# DIGITAL_OUTPUTS_BLOCK_B.net
KiCad netlist of a schematic drawn in Altium Designer
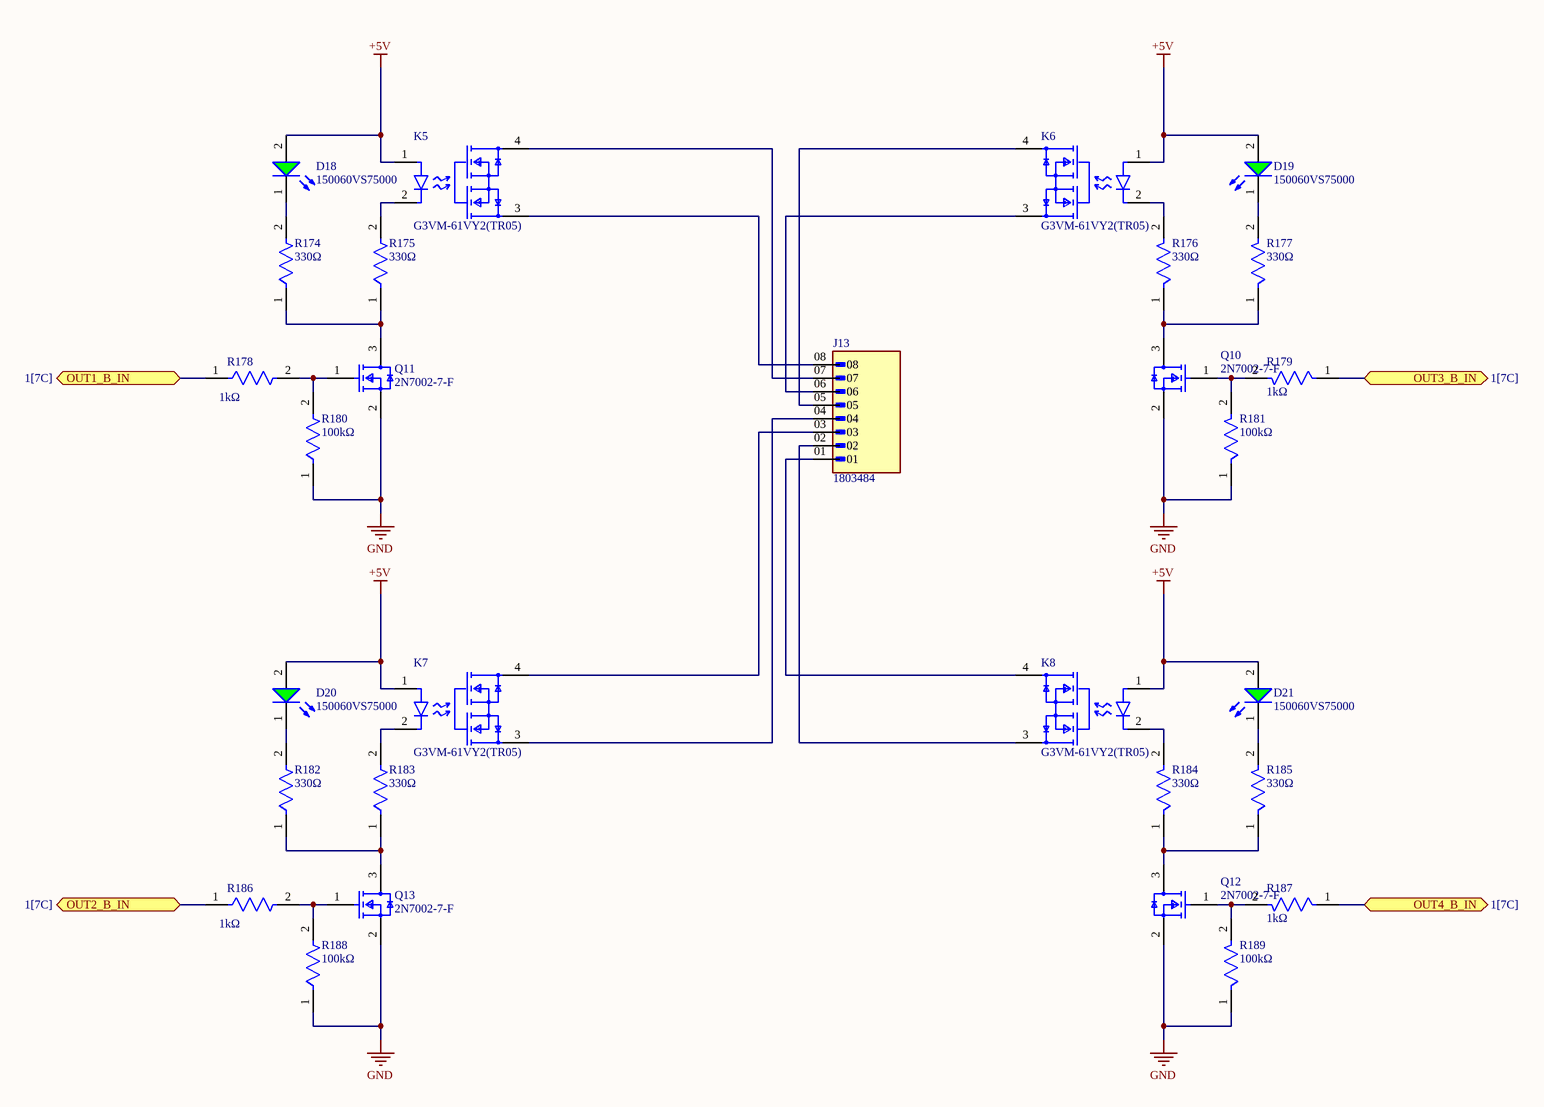
[diagram p0: DIGITAL_OUTPUTS_BLOCK_B.SchDoc]

(export (version "E")
  (design (tool "Eeschema 10.0.6"))
  (components
    (comp (ref "D18")
      (value "150060VS75000")
      (footprint "WL-SMCW_0603_150060xx75000")
      (libsource (lib "Altium Content Vault") (part "LED_Green_2A-1K"))
    )
    (comp (ref "D19")
      (value "150060VS75000")
      (footprint "WL-SMCW_0603_150060xx75000")
      (libsource (lib "Altium Content Vault") (part "LED_Green_2A-1K"))
    )
    (comp (ref "D20")
      (value "150060VS75000")
      (footprint "WL-SMCW_0603_150060xx75000")
      (libsource (lib "Altium Content Vault") (part "LED_Green_2A-1K"))
    )
    (comp (ref "D21")
      (value "150060VS75000")
      (footprint "WL-SMCW_0603_150060xx75000")
      (libsource (lib "Altium Content Vault") (part "LED_Green_2A-1K"))
    )
    (comp (ref "J13")
      (value "1803484")
      (footprint "1803484:PHOENIX_1803484")
      (fields (field (name "MF") "{'manufacturer': u'Phoenix Contact'}"))
      (libsource (lib "*") (part "1803484"))
    )
    (comp (ref "K5")
      (value "G3VM-61VY2(TR05)")
      (footprint "FP-G3VM-61VY2_TR05-MFG")
      (description "SSR RELAY SPST-NO 500MA 0-60V")
      (libsource (lib "Altium Content Vault") (part "39108d2c2fe9c6c4263f1aa8ae40286"))
    )
    (comp (ref "K6")
      (value "G3VM-61VY2(TR05)")
      (footprint "FP-G3VM-61VY2_TR05-MFG")
      (description "SSR RELAY SPST-NO 500MA 0-60V")
      (libsource (lib "Altium Content Vault") (part "39108d2c2fe9c6c4263f1aa8ae40286"))
    )
    (comp (ref "K7")
      (value "G3VM-61VY2(TR05)")
      (footprint "FP-G3VM-61VY2_TR05-MFG")
      (description "SSR RELAY SPST-NO 500MA 0-60V")
      (libsource (lib "Altium Content Vault") (part "39108d2c2fe9c6c4263f1aa8ae40286"))
    )
    (comp (ref "K8")
      (value "G3VM-61VY2(TR05)")
      (footprint "FP-G3VM-61VY2_TR05-MFG")
      (description "SSR RELAY SPST-NO 500MA 0-60V")
      (libsource (lib "Altium Content Vault") (part "39108d2c2fe9c6c4263f1aa8ae40286"))
    )
    (comp (ref "Q10")
      (value "2N7002-7-F")
      (footprint "FP-SOT23-IPC_A")
      (description "MOSFET N-CH 60V 115MA SOT23-3")
      (fields (field (name "VOLTAGE") "60V"))
      (libsource (lib "Altium Content Vault") (part "3b9c635fedb024a5347a57b145af9cc"))
    )
    (comp (ref "Q11")
      (value "2N7002-7-F")
      (footprint "FP-SOT23-IPC_A")
      (description "MOSFET N-CH 60V 115MA SOT23-3")
      (fields (field (name "VOLTAGE") "60V"))
      (libsource (lib "Altium Content Vault") (part "3b9c635fedb024a5347a57b145af9cc"))
    )
    (comp (ref "Q12")
      (value "2N7002-7-F")
      (footprint "FP-SOT23-IPC_A")
      (description "MOSFET N-CH 60V 115MA SOT23-3")
      (fields (field (name "VOLTAGE") "60V"))
      (libsource (lib "Altium Content Vault") (part "3b9c635fedb024a5347a57b145af9cc"))
    )
    (comp (ref "Q13")
      (value "2N7002-7-F")
      (footprint "FP-SOT23-IPC_A")
      (description "MOSFET N-CH 60V 115MA SOT23-3")
      (fields (field (name "VOLTAGE") "60V"))
      (libsource (lib "Altium Content Vault") (part "3b9c635fedb024a5347a57b145af9cc"))
    )
    (comp (ref "R174")
      (value "CRCW0603330RFKEA")
      (footprint "FP-CRCW0603-e3-MFG")
      (description "RES Thick Film, 330Ω, 1%, 0.1W, 100ppm/°C, 0603")
      (fields (field (name "TOLERANCE") "1%") (field (name "RESISTANCE") "330Ω"))
      (libsource (lib "Altium Content Vault") (part "1029c3af85768c4190bb7ad29bc67b5"))
    )
    (comp (ref "R175")
      (value "CRCW0603330RFKEA")
      (footprint "FP-CRCW0603-e3-MFG")
      (description "RES Thick Film, 330Ω, 1%, 0.1W, 100ppm/°C, 0603")
      (fields (field (name "TOLERANCE") "1%") (field (name "RESISTANCE") "330Ω"))
      (libsource (lib "Altium Content Vault") (part "1029c3af85768c4190bb7ad29bc67b5"))
    )
    (comp (ref "R176")
      (value "CRCW0603330RFKEA")
      (footprint "FP-CRCW0603-e3-MFG")
      (description "RES Thick Film, 330Ω, 1%, 0.1W, 100ppm/°C, 0603")
      (fields (field (name "TOLERANCE") "1%") (field (name "RESISTANCE") "330Ω"))
      (libsource (lib "Altium Content Vault") (part "1029c3af85768c4190bb7ad29bc67b5"))
    )
    (comp (ref "R177")
      (value "CRCW0603330RFKEA")
      (footprint "FP-CRCW0603-e3-MFG")
      (description "RES Thick Film, 330Ω, 1%, 0.1W, 100ppm/°C, 0603")
      (fields (field (name "TOLERANCE") "1%") (field (name "RESISTANCE") "330Ω"))
      (libsource (lib "Altium Content Vault") (part "1029c3af85768c4190bb7ad29bc67b5"))
    )
    (comp (ref "R178")
      (value "AC0603FR-071KL")
      (footprint "FP-AC0603-IPC_B")
      (description "RES 1kΩ 1.00% 0.1W 0603")
      (fields (field (name "TOLERANCE") "1%") (field (name "RESISTANCE") "1kΩ"))
      (libsource (lib "Altium Content Vault") (part "1029c3af85768c4190bb7ad29bc67b5"))
    )
    (comp (ref "R179")
      (value "AC0603FR-071KL")
      (footprint "FP-AC0603-IPC_B")
      (description "RES 1kΩ 1.00% 0.1W 0603")
      (fields (field (name "TOLERANCE") "1%") (field (name "RESISTANCE") "1kΩ"))
      (libsource (lib "Altium Content Vault") (part "1029c3af85768c4190bb7ad29bc67b5"))
    )
    (comp (ref "R180")
      (value "CRCW0603100KFKEC")
      (footprint "FP-CRCW0603-e3-IPC_B")
      (description "RES Thick Film, 100kΩ, 1%, 0.1W, 100ppm/°C, 0603")
      (fields (field (name "RESISTANCE") "100kΩ") (field (name "TOLERANCE") "1%"))
      (libsource (lib "Altium Content Vault") (part "1029c3af85768c4190bb7ad29bc67b5"))
    )
    (comp (ref "R181")
      (value "CRCW0603100KFKEC")
      (footprint "FP-CRCW0603-e3-IPC_B")
      (description "RES Thick Film, 100kΩ, 1%, 0.1W, 100ppm/°C, 0603")
      (fields (field (name "RESISTANCE") "100kΩ") (field (name "TOLERANCE") "1%"))
      (libsource (lib "Altium Content Vault") (part "1029c3af85768c4190bb7ad29bc67b5"))
    )
    (comp (ref "R182")
      (value "CRCW0603330RFKEA")
      (footprint "FP-CRCW0603-e3-MFG")
      (description "RES Thick Film, 330Ω, 1%, 0.1W, 100ppm/°C, 0603")
      (fields (field (name "TOLERANCE") "1%") (field (name "RESISTANCE") "330Ω"))
      (libsource (lib "Altium Content Vault") (part "1029c3af85768c4190bb7ad29bc67b5"))
    )
    (comp (ref "R183")
      (value "CRCW0603330RFKEA")
      (footprint "FP-CRCW0603-e3-MFG")
      (description "RES Thick Film, 330Ω, 1%, 0.1W, 100ppm/°C, 0603")
      (fields (field (name "TOLERANCE") "1%") (field (name "RESISTANCE") "330Ω"))
      (libsource (lib "Altium Content Vault") (part "1029c3af85768c4190bb7ad29bc67b5"))
    )
    (comp (ref "R184")
      (value "CRCW0603330RFKEA")
      (footprint "FP-CRCW0603-e3-MFG")
      (description "RES Thick Film, 330Ω, 1%, 0.1W, 100ppm/°C, 0603")
      (fields (field (name "TOLERANCE") "1%") (field (name "RESISTANCE") "330Ω"))
      (libsource (lib "Altium Content Vault") (part "1029c3af85768c4190bb7ad29bc67b5"))
    )
    (comp (ref "R185")
      (value "CRCW0603330RFKEA")
      (footprint "FP-CRCW0603-e3-MFG")
      (description "RES Thick Film, 330Ω, 1%, 0.1W, 100ppm/°C, 0603")
      (fields (field (name "TOLERANCE") "1%") (field (name "RESISTANCE") "330Ω"))
      (libsource (lib "Altium Content Vault") (part "1029c3af85768c4190bb7ad29bc67b5"))
    )
    (comp (ref "R186")
      (value "AC0603FR-071KL")
      (footprint "FP-AC0603-IPC_B")
      (description "RES 1kΩ 1.00% 0.1W 0603")
      (fields (field (name "TOLERANCE") "1%") (field (name "RESISTANCE") "1kΩ"))
      (libsource (lib "Altium Content Vault") (part "1029c3af85768c4190bb7ad29bc67b5"))
    )
    (comp (ref "R187")
      (value "AC0603FR-071KL")
      (footprint "FP-AC0603-IPC_B")
      (description "RES 1kΩ 1.00% 0.1W 0603")
      (fields (field (name "TOLERANCE") "1%") (field (name "RESISTANCE") "1kΩ"))
      (libsource (lib "Altium Content Vault") (part "1029c3af85768c4190bb7ad29bc67b5"))
    )
    (comp (ref "R188")
      (value "CRCW0603100KFKEC")
      (footprint "FP-CRCW0603-e3-IPC_B")
      (description "RES Thick Film, 100kΩ, 1%, 0.1W, 100ppm/°C, 0603")
      (fields (field (name "RESISTANCE") "100kΩ") (field (name "TOLERANCE") "1%"))
      (libsource (lib "Altium Content Vault") (part "1029c3af85768c4190bb7ad29bc67b5"))
    )
    (comp (ref "R189")
      (value "CRCW0603100KFKEC")
      (footprint "FP-CRCW0603-e3-IPC_B")
      (description "RES Thick Film, 100kΩ, 1%, 0.1W, 100ppm/°C, 0603")
      (fields (field (name "RESISTANCE") "100kΩ") (field (name "TOLERANCE") "1%"))
      (libsource (lib "Altium Content Vault") (part "1029c3af85768c4190bb7ad29bc67b5"))
    )
  )
  (nets
    (net (code "1") (name "+5V") (class "Default")
      (node (ref "D18") (pin "2") (pinfunction "A_2") (pintype "passive"))
      (node (ref "D19") (pin "2") (pinfunction "A_2") (pintype "passive"))
      (node (ref "D20") (pin "2") (pinfunction "A_2") (pintype "passive"))
      (node (ref "D21") (pin "2") (pinfunction "A_2") (pintype "passive"))
      (node (ref "K5") (pin "1") (pinfunction "A_1") (pintype "passive"))
      (node (ref "K6") (pin "1") (pinfunction "A_1") (pintype "passive"))
      (node (ref "K7") (pin "1") (pinfunction "A_1") (pintype "passive"))
      (node (ref "K8") (pin "1") (pinfunction "A_1") (pintype "passive"))
    )
    (net (code "2") (name "/OUT1_B_IN") (class "Default")
      (node (ref "R178") (pin "1") (pinfunction "1_1") (pintype "passive"))
    )
    (net (code "3") (name "/OUT2_B_IN") (class "Default")
      (node (ref "R186") (pin "1") (pinfunction "1_1") (pintype "passive"))
    )
    (net (code "4") (name "/OUT3_B_IN") (class "Default")
      (node (ref "R179") (pin "1") (pinfunction "1_1") (pintype "passive"))
    )
    (net (code "5") (name "/OUT4_B_IN") (class "Default")
      (node (ref "R187") (pin "1") (pinfunction "1_1") (pintype "passive"))
    )
    (net (code "6") (name "GND") (class "Default")
      (node (ref "Q10") (pin "2") (pinfunction "S_2") (pintype "passive"))
      (node (ref "Q11") (pin "2") (pinfunction "S_2") (pintype "passive"))
      (node (ref "Q12") (pin "2") (pinfunction "S_2") (pintype "passive"))
      (node (ref "Q13") (pin "2") (pinfunction "S_2") (pintype "passive"))
      (node (ref "R180") (pin "1") (pinfunction "1_1") (pintype "passive"))
      (node (ref "R181") (pin "1") (pinfunction "1_1") (pintype "passive"))
      (node (ref "R188") (pin "1") (pinfunction "1_1") (pintype "passive"))
      (node (ref "R189") (pin "1") (pinfunction "1_1") (pintype "passive"))
    )
    (net (code "7") (name "Net-(D18-K)") (class "Default")
      (node (ref "D18") (pin "1") (pinfunction "K_1") (pintype "passive"))
      (node (ref "R174") (pin "2") (pinfunction "2_2") (pintype "passive"))
    )
    (net (code "8") (name "Net-(D19-K)") (class "Default")
      (node (ref "D19") (pin "1") (pinfunction "K_1") (pintype "passive"))
      (node (ref "R177") (pin "2") (pinfunction "2_2") (pintype "passive"))
    )
    (net (code "9") (name "Net-(D20-K)") (class "Default")
      (node (ref "D20") (pin "1") (pinfunction "K_1") (pintype "passive"))
      (node (ref "R182") (pin "2") (pinfunction "2_2") (pintype "passive"))
    )
    (net (code "10") (name "Net-(D21-K)") (class "Default")
      (node (ref "D21") (pin "1") (pinfunction "K_1") (pintype "passive"))
      (node (ref "R185") (pin "2") (pinfunction "2_2") (pintype "passive"))
    )
    (net (code "11") (name "Net-(K5-1_DRAIN)") (class "Default")
      (node (ref "J13") (pin "08") (pinfunction "08_08") (pintype "passive"))
      (node (ref "K5") (pin "3") (pinfunction "1_DRAIN_3") (pintype "passive"))
    )
    (net (code "12") (name "Net-(K5-2_DRAIN)") (class "Default")
      (node (ref "J13") (pin "07") (pinfunction "07_07") (pintype "passive"))
      (node (ref "K5") (pin "4") (pinfunction "2_DRAIN_4") (pintype "passive"))
    )
    (net (code "13") (name "Net-(K5-C)") (class "Default")
      (node (ref "K5") (pin "2") (pinfunction "C_2") (pintype "passive"))
      (node (ref "R175") (pin "2") (pinfunction "2_2") (pintype "passive"))
    )
    (net (code "14") (name "Net-(K6-1_DRAIN)") (class "Default")
      (node (ref "J13") (pin "06") (pinfunction "06_06") (pintype "passive"))
      (node (ref "K6") (pin "3") (pinfunction "1_DRAIN_3") (pintype "passive"))
    )
    (net (code "15") (name "Net-(K6-2_DRAIN)") (class "Default")
      (node (ref "J13") (pin "05") (pinfunction "05_05") (pintype "passive"))
      (node (ref "K6") (pin "4") (pinfunction "2_DRAIN_4") (pintype "passive"))
    )
    (net (code "16") (name "Net-(K6-C)") (class "Default")
      (node (ref "K6") (pin "2") (pinfunction "C_2") (pintype "passive"))
      (node (ref "R176") (pin "2") (pinfunction "2_2") (pintype "passive"))
    )
    (net (code "17") (name "Net-(K7-1_DRAIN)") (class "Default")
      (node (ref "J13") (pin "04") (pinfunction "04_04") (pintype "passive"))
      (node (ref "K7") (pin "3") (pinfunction "1_DRAIN_3") (pintype "passive"))
    )
    (net (code "18") (name "Net-(K7-2_DRAIN)") (class "Default")
      (node (ref "J13") (pin "03") (pinfunction "03_03") (pintype "passive"))
      (node (ref "K7") (pin "4") (pinfunction "2_DRAIN_4") (pintype "passive"))
    )
    (net (code "19") (name "Net-(K7-C)") (class "Default")
      (node (ref "K7") (pin "2") (pinfunction "C_2") (pintype "passive"))
      (node (ref "R183") (pin "2") (pinfunction "2_2") (pintype "passive"))
    )
    (net (code "20") (name "Net-(K8-1_DRAIN)") (class "Default")
      (node (ref "J13") (pin "02") (pinfunction "02_02") (pintype "passive"))
      (node (ref "K8") (pin "3") (pinfunction "1_DRAIN_3") (pintype "passive"))
    )
    (net (code "21") (name "Net-(K8-2_DRAIN)") (class "Default")
      (node (ref "J13") (pin "01") (pinfunction "01_01") (pintype "passive"))
      (node (ref "K8") (pin "4") (pinfunction "2_DRAIN_4") (pintype "passive"))
    )
    (net (code "22") (name "Net-(K8-C)") (class "Default")
      (node (ref "K8") (pin "2") (pinfunction "C_2") (pintype "passive"))
      (node (ref "R184") (pin "2") (pinfunction "2_2") (pintype "passive"))
    )
    (net (code "23") (name "Net-(Q10-D)") (class "Default")
      (node (ref "Q10") (pin "3") (pinfunction "D_3") (pintype "passive"))
      (node (ref "R176") (pin "1") (pinfunction "1_1") (pintype "passive"))
      (node (ref "R177") (pin "1") (pinfunction "1_1") (pintype "passive"))
    )
    (net (code "24") (name "Net-(Q10-G)") (class "Default")
      (node (ref "Q10") (pin "1") (pinfunction "G_1") (pintype "passive"))
      (node (ref "R179") (pin "2") (pinfunction "2_2") (pintype "passive"))
      (node (ref "R181") (pin "2") (pinfunction "2_2") (pintype "passive"))
    )
    (net (code "25") (name "Net-(Q11-D)") (class "Default")
      (node (ref "Q11") (pin "3") (pinfunction "D_3") (pintype "passive"))
      (node (ref "R174") (pin "1") (pinfunction "1_1") (pintype "passive"))
      (node (ref "R175") (pin "1") (pinfunction "1_1") (pintype "passive"))
    )
    (net (code "26") (name "Net-(Q11-G)") (class "Default")
      (node (ref "Q11") (pin "1") (pinfunction "G_1") (pintype "passive"))
      (node (ref "R178") (pin "2") (pinfunction "2_2") (pintype "passive"))
      (node (ref "R180") (pin "2") (pinfunction "2_2") (pintype "passive"))
    )
    (net (code "27") (name "Net-(Q12-D)") (class "Default")
      (node (ref "Q12") (pin "3") (pinfunction "D_3") (pintype "passive"))
      (node (ref "R184") (pin "1") (pinfunction "1_1") (pintype "passive"))
      (node (ref "R185") (pin "1") (pinfunction "1_1") (pintype "passive"))
    )
    (net (code "28") (name "Net-(Q12-G)") (class "Default")
      (node (ref "Q12") (pin "1") (pinfunction "G_1") (pintype "passive"))
      (node (ref "R187") (pin "2") (pinfunction "2_2") (pintype "passive"))
      (node (ref "R189") (pin "2") (pinfunction "2_2") (pintype "passive"))
    )
    (net (code "29") (name "Net-(Q13-D)") (class "Default")
      (node (ref "Q13") (pin "3") (pinfunction "D_3") (pintype "passive"))
      (node (ref "R182") (pin "1") (pinfunction "1_1") (pintype "passive"))
      (node (ref "R183") (pin "1") (pinfunction "1_1") (pintype "passive"))
    )
    (net (code "30") (name "Net-(Q13-G)") (class "Default")
      (node (ref "Q13") (pin "1") (pinfunction "G_1") (pintype "passive"))
      (node (ref "R186") (pin "2") (pinfunction "2_2") (pintype "passive"))
      (node (ref "R188") (pin "2") (pinfunction "2_2") (pintype "passive"))
    )
  )
)
